# mcu.net
KiCad netlist of a schematic drawn in Altium Designer
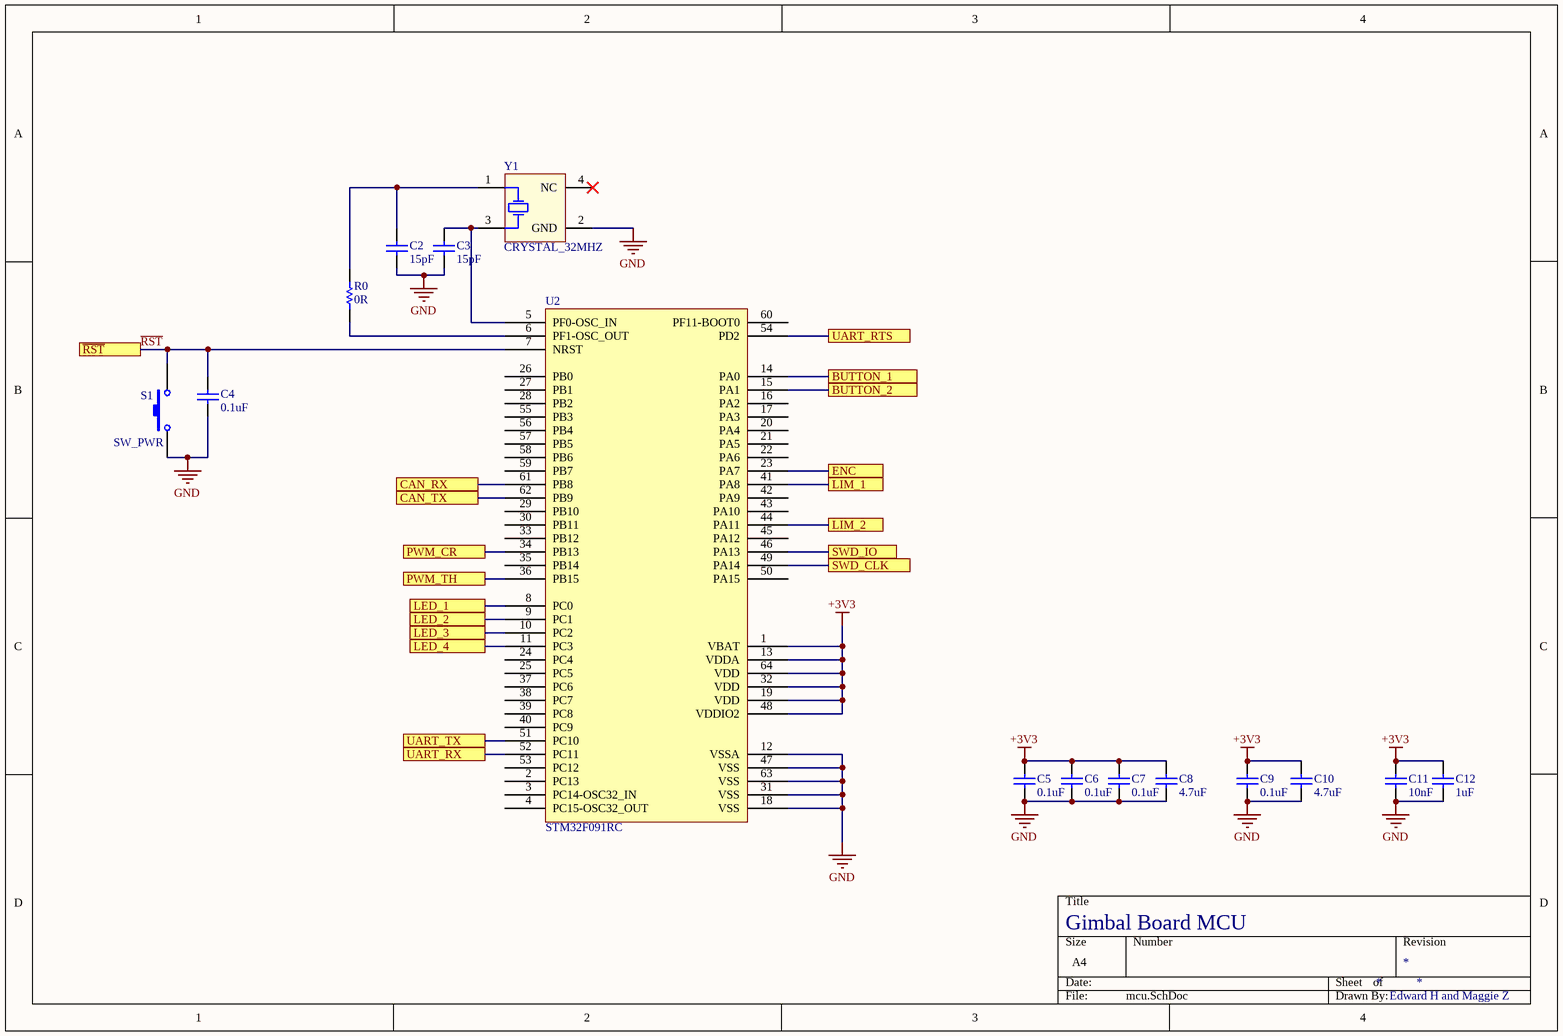
[diagram p0: mcu.SchDoc]

(export (version "E")
  (design (tool "Eeschema 10.0.6"))
  (components
    (comp (ref "C2")
      (value "15pF")
      (footprint "CAPC0603(1608)55_N")
      (description "CAP CER 15PF 250V NPO 0603")
      (fields (field (name "MANUFACTURER") "Yageo") (field (name "MPN") "AC0603JRNPOYBN150"))
      (libsource (lib "UWRT_Schematic_Library_2019") (part "CAP_15pF_0603"))
    )
    (comp (ref "C3")
      (value "15pF")
      (footprint "CAPC0603(1608)55_N")
      (description "CAP CER 15PF 250V NPO 0603")
      (fields (field (name "MANUFACTURER") "Yageo") (field (name "MPN") "AC0603JRNPOYBN150"))
      (libsource (lib "UWRT_Schematic_Library_2019") (part "CAP_15pF_0603"))
    )
    (comp (ref "C4")
      (value "0.1uF")
      (footprint "CAPC0603(1608)55_N")
      (description "CAP CER 0.1UF 16V X7R 0603")
      (fields (field (name "MANUFACTURER") "Yageo") (field (name "MPN") "CC0603KRX7R7BB104"))
      (libsource (lib "UWRT_Schematic_Library_2019") (part "CAP_0.1uF_16V_0603"))
    )
    (comp (ref "C5")
      (value "0.1uF")
      (footprint "CAPC0603(1608)55_N")
      (description "CAP CER 0.1UF 16V X7R 0603")
      (fields (field (name "MANUFACTURER") "Yageo") (field (name "MPN") "CC0603KRX7R7BB104"))
      (libsource (lib "UWRT_Schematic_Library_2019") (part "CAP_0.1uF_16V_0603"))
    )
    (comp (ref "C6")
      (value "0.1uF")
      (footprint "CAPC0603(1608)55_N")
      (description "CAP CER 0.1UF 16V X7R 0603")
      (fields (field (name "MANUFACTURER") "Yageo") (field (name "MPN") "CC0603KRX7R7BB104"))
      (libsource (lib "UWRT_Schematic_Library_2019") (part "CAP_0.1uF_16V_0603"))
    )
    (comp (ref "C7")
      (value "0.1uF")
      (footprint "CAPC0603(1608)55_N")
      (description "CAP CER 0.1UF 16V X7R 0603")
      (fields (field (name "MANUFACTURER") "Yageo") (field (name "MPN") "CC0603KRX7R7BB104"))
      (libsource (lib "UWRT_Schematic_Library_2019") (part "CAP_0.1uF_16V_0603"))
    )
    (comp (ref "C8")
      (value "4.7uF")
      (footprint "CAPC0603(1608)55_N")
      (description "CAP CER 4.7UF 6.3V X5R 0603")
      (fields (field (name "MANUFACTURER") "Yageo") (field (name "MPN") "CC0603KRX5R5BB475"))
      (libsource (lib "UWRT_Schematic_Library_2019") (part "CAP_4.7uF_0603"))
    )
    (comp (ref "C9")
      (value "0.1uF")
      (footprint "CAPC0603(1608)55_N")
      (description "CAP CER 0.1UF 16V X7R 0603")
      (fields (field (name "MANUFACTURER") "Yageo") (field (name "MPN") "CC0603KRX7R7BB104"))
      (libsource (lib "UWRT_Schematic_Library_2019") (part "CAP_0.1uF_16V_0603"))
    )
    (comp (ref "C10")
      (value "4.7uF")
      (footprint "CAPC0603(1608)55_N")
      (description "CAP CER 4.7UF 6.3V X5R 0603")
      (fields (field (name "MANUFACTURER") "Yageo") (field (name "MPN") "CC0603KRX5R5BB475"))
      (libsource (lib "UWRT_Schematic_Library_2019") (part "CAP_4.7uF_0603"))
    )
    (comp (ref "C11")
      (value "10nF")
      (footprint "CAPC0603(1608)55_N")
      (description "CAP CER 10000PF 16V X7R 0603")
      (fields (field (name "MANUFACTURER") "Yageo") (field (name "MPN") "CC0603KRX7R7BB103"))
      (libsource (lib "UWRT_Schematic_Library_2019") (part "CAP_10nF_0603"))
    )
    (comp (ref "C12")
      (value "1uF")
      (footprint "CAPC0603(1608)55_N")
      (description "CAP CER 1UF 16V Y5V 0603")
      (fields (field (name "MANUFACTURER") "Yageo") (field (name "MPN") "CC0603ZRY5V7BB105"))
      (libsource (lib "UWRT_Schematic_Library_2019") (part "CAP_1uF_16V_0603"))
    )
    (comp (ref "R0")
      (value "0R")
      (footprint "RESC0603(1608)_N")
      (description "RES SMD 0 OHM JUMPER 1/10W 0603")
      (fields (field (name "MANUFACTURER") "Yageo") (field (name "MPN") "RC0603JR-070RL"))
      (libsource (lib "UWRT_Schematic_Library_2019") (part "RES_0R_0603"))
    )
    (comp (ref "S1")
      (value "SW_PWR")
      (footprint "PTS830GM140")
      (description "Power Switch (Red)")
      (fields
        (field (name "MPN") "PTS830GM140 SMTR LFS")
        (field (name "DIGIKEY PART NUMBER") "CKN10587CT-ND")
      )
      (libsource (lib "UWRT_Schematic_Library_2019") (part "SW_PWR"))
    )
    (comp (ref "U2")
      (value "STM32F091RC")
      (footprint "UWRT_Footprint_Library_2019:STM_LQFP64_N")
      (fields
        (field (name "MANUFACTURER") "STMicroelectronics")
        (field (name "DIGIKEY PART NUMBER") "497-15167-ND")
      )
      (libsource (lib "UWRT_Schematic_Library_2019") (part "STM32F091RC"))
    )
    (comp (ref "Y1")
      (value "CRYSTAL_32MHZ")
      (footprint "AVX-CX2520DB32000D0GEJZ1-4_V")
      (description "CRYSTAL 32MHZ 8PF SMD")
      (fields
        (field (name "MANUFACTURER") "Kyocera International Inc. Electronic Components")
        (field (name "MPN") "CX2520DB32000D0GPSC1")
      )
      (libsource (lib "UWRT_Schematic_Library_2019") (part "CRYSTAL_32MHZ"))
    )
  )
  (nets
    (net (code "1") (name "+3V3") (class "Default")
      (node (ref "C10") (pin "2") (pinfunction "2_2") (pintype "passive"))
      (node (ref "C11") (pin "2") (pinfunction "2_2") (pintype "passive"))
      (node (ref "C12") (pin "2") (pinfunction "2_2") (pintype "passive"))
      (node (ref "C5") (pin "1") (pinfunction "1_1") (pintype "passive"))
      (node (ref "C6") (pin "1") (pinfunction "1_1") (pintype "passive"))
      (node (ref "C7") (pin "1") (pinfunction "1_1") (pintype "passive"))
      (node (ref "C8") (pin "2") (pinfunction "2_2") (pintype "passive"))
      (node (ref "C9") (pin "1") (pinfunction "1_1") (pintype "passive"))
      (node (ref "U2") (pin "1") (pinfunction "VBAT_1") (pintype "passive"))
      (node (ref "U2") (pin "13") (pinfunction "VDDA_13") (pintype "passive"))
      (node (ref "U2") (pin "19") (pinfunction "VDD_19") (pintype "passive"))
      (node (ref "U2") (pin "32") (pinfunction "VDD_32") (pintype "passive"))
      (node (ref "U2") (pin "48") (pinfunction "VDDIO2_48") (pintype "passive"))
      (node (ref "U2") (pin "64") (pinfunction "VDD_64") (pintype "passive"))
    )
    (net (code "2") (name "/BUTTON_1") (class "Default")
      (node (ref "U2") (pin "14") (pinfunction "PA0_14") (pintype "passive"))
    )
    (net (code "3") (name "/BUTTON_2") (class "Default")
      (node (ref "U2") (pin "15") (pinfunction "PA1_15") (pintype "passive"))
    )
    (net (code "4") (name "/CAN_RX") (class "Default")
      (node (ref "U2") (pin "61") (pinfunction "PB8_61") (pintype "passive"))
    )
    (net (code "5") (name "/CAN_TX") (class "Default")
      (node (ref "U2") (pin "62") (pinfunction "PB9_62") (pintype "passive"))
    )
    (net (code "6") (name "/ENC") (class "Default")
      (node (ref "U2") (pin "23") (pinfunction "PA7_23") (pintype "passive"))
    )
    (net (code "7") (name "/LED_1") (class "Default")
      (node (ref "U2") (pin "8") (pinfunction "PC0_8") (pintype "passive"))
    )
    (net (code "8") (name "/LED_2") (class "Default")
      (node (ref "U2") (pin "9") (pinfunction "PC1_9") (pintype "passive"))
    )
    (net (code "9") (name "/LED_3") (class "Default")
      (node (ref "U2") (pin "10") (pinfunction "PC2_10") (pintype "passive"))
    )
    (net (code "10") (name "/LED_4") (class "Default")
      (node (ref "U2") (pin "11") (pinfunction "PC3_11") (pintype "passive"))
    )
    (net (code "11") (name "/LIM_1") (class "Default")
      (node (ref "U2") (pin "41") (pinfunction "PA8_41") (pintype "passive"))
    )
    (net (code "12") (name "/LIM_2") (class "Default")
      (node (ref "U2") (pin "44") (pinfunction "PA11_44") (pintype "passive"))
    )
    (net (code "13") (name "/PWM_CR") (class "Default")
      (node (ref "U2") (pin "34") (pinfunction "PB13_34") (pintype "passive"))
    )
    (net (code "14") (name "/PWM_TH") (class "Default")
      (node (ref "U2") (pin "36") (pinfunction "PB15_36") (pintype "passive"))
    )
    (net (code "15") (name "/SWD_CLK") (class "Default")
      (node (ref "U2") (pin "49") (pinfunction "PA14_49") (pintype "passive"))
    )
    (net (code "16") (name "/SWD_IO") (class "Default")
      (node (ref "U2") (pin "46") (pinfunction "PA13_46") (pintype "passive"))
    )
    (net (code "17") (name "/UART_RTS") (class "Default")
      (node (ref "U2") (pin "54") (pinfunction "PD2_54") (pintype "passive"))
    )
    (net (code "18") (name "/UART_RX") (class "Default")
      (node (ref "U2") (pin "52") (pinfunction "PC11_52") (pintype "passive"))
    )
    (net (code "19") (name "/UART_TX") (class "Default")
      (node (ref "U2") (pin "51") (pinfunction "PC10_51") (pintype "passive"))
    )
    (net (code "20") (name "/~{RST}") (class "Default")
      (node (ref "C4") (pin "2") (pinfunction "2_2") (pintype "passive"))
      (node (ref "S1") (pin "2") (pinfunction "2_2") (pintype "passive"))
      (node (ref "U2") (pin "7") (pinfunction "NRST_7") (pintype "passive"))
    )
    (net (code "21") (name "GND") (class "Default")
      (node (ref "C10") (pin "1") (pinfunction "1_1") (pintype "passive"))
      (node (ref "C11") (pin "1") (pinfunction "1_1") (pintype "passive"))
      (node (ref "C12") (pin "1") (pinfunction "1_1") (pintype "passive"))
      (node (ref "C2") (pin "1") (pinfunction "1_1") (pintype "passive"))
      (node (ref "C3") (pin "1") (pinfunction "1_1") (pintype "passive"))
      (node (ref "C4") (pin "1") (pinfunction "1_1") (pintype "passive"))
      (node (ref "C5") (pin "2") (pinfunction "2_2") (pintype "passive"))
      (node (ref "C6") (pin "2") (pinfunction "2_2") (pintype "passive"))
      (node (ref "C7") (pin "2") (pinfunction "2_2") (pintype "passive"))
      (node (ref "C8") (pin "1") (pinfunction "1_1") (pintype "passive"))
      (node (ref "C9") (pin "2") (pinfunction "2_2") (pintype "passive"))
      (node (ref "S1") (pin "1") (pinfunction "1_1") (pintype "passive"))
      (node (ref "U2") (pin "12") (pinfunction "VSSA_12") (pintype "passive"))
      (node (ref "U2") (pin "18") (pinfunction "VSS_18") (pintype "passive"))
      (node (ref "U2") (pin "31") (pinfunction "VSS_31") (pintype "passive"))
      (node (ref "U2") (pin "47") (pinfunction "VSS_47") (pintype "passive"))
      (node (ref "U2") (pin "63") (pinfunction "VSS_63") (pintype "passive"))
      (node (ref "Y1") (pin "2") (pinfunction "GND_2") (pintype "power_in"))
    )
    (net (code "22") (name "Net-(C2-Pad2)") (class "Default")
      (node (ref "C2") (pin "2") (pinfunction "2_2") (pintype "passive"))
      (node (ref "R0") (pin "2") (pinfunction "2_2") (pintype "passive"))
      (node (ref "Y1") (pin "1") (pinfunction "HOT_1") (pintype "passive"))
    )
    (net (code "23") (name "Net-(U2-PF0-OSC_IN)") (class "Default")
      (node (ref "C3") (pin "2") (pinfunction "2_2") (pintype "passive"))
      (node (ref "U2") (pin "5") (pinfunction "PF0-OSC_IN_5") (pintype "passive"))
      (node (ref "Y1") (pin "3") (pinfunction "HOT_3") (pintype "passive"))
    )
    (net (code "24") (name "Net-(U2-PF1-OSC_OUT)") (class "Default")
      (node (ref "R0") (pin "1") (pinfunction "1_1") (pintype "passive"))
      (node (ref "U2") (pin "6") (pinfunction "PF1-OSC_OUT_6") (pintype "passive"))
    )
    (net (code "25") (name "unconnected-(U2-PA2-Pad16)") (class "Default")
      (node (ref "U2") (pin "16") (pinfunction "PA2_16") (pintype "passive"))
    )
    (net (code "26") (name "unconnected-(U2-PA3-Pad17)") (class "Default")
      (node (ref "U2") (pin "17") (pinfunction "PA3_17") (pintype "passive"))
    )
    (net (code "27") (name "unconnected-(U2-PA4-Pad20)") (class "Default")
      (node (ref "U2") (pin "20") (pinfunction "PA4_20") (pintype "passive"))
    )
    (net (code "28") (name "unconnected-(U2-PA5-Pad21)") (class "Default")
      (node (ref "U2") (pin "21") (pinfunction "PA5_21") (pintype "passive"))
    )
    (net (code "29") (name "unconnected-(U2-PA6-Pad22)") (class "Default")
      (node (ref "U2") (pin "22") (pinfunction "PA6_22") (pintype "passive"))
    )
    (net (code "30") (name "unconnected-(U2-PA9-Pad42)") (class "Default")
      (node (ref "U2") (pin "42") (pinfunction "PA9_42") (pintype "passive"))
    )
    (net (code "31") (name "unconnected-(U2-PA10-Pad43)") (class "Default")
      (node (ref "U2") (pin "43") (pinfunction "PA10_43") (pintype "passive"))
    )
    (net (code "32") (name "unconnected-(U2-PA12-Pad45)") (class "Default")
      (node (ref "U2") (pin "45") (pinfunction "PA12_45") (pintype "passive"))
    )
    (net (code "33") (name "unconnected-(U2-PA15-Pad50)") (class "Default")
      (node (ref "U2") (pin "50") (pinfunction "PA15_50") (pintype "passive"))
    )
    (net (code "34") (name "unconnected-(U2-PB0-Pad26)") (class "Default")
      (node (ref "U2") (pin "26") (pinfunction "PB0_26") (pintype "passive"))
    )
    (net (code "35") (name "unconnected-(U2-PB1-Pad27)") (class "Default")
      (node (ref "U2") (pin "27") (pinfunction "PB1_27") (pintype "passive"))
    )
    (net (code "36") (name "unconnected-(U2-PB2-Pad28)") (class "Default")
      (node (ref "U2") (pin "28") (pinfunction "PB2_28") (pintype "passive"))
    )
    (net (code "37") (name "unconnected-(U2-PB3-Pad55)") (class "Default")
      (node (ref "U2") (pin "55") (pinfunction "PB3_55") (pintype "passive"))
    )
    (net (code "38") (name "unconnected-(U2-PB4-Pad56)") (class "Default")
      (node (ref "U2") (pin "56") (pinfunction "PB4_56") (pintype "passive"))
    )
    (net (code "39") (name "unconnected-(U2-PB5-Pad57)") (class "Default")
      (node (ref "U2") (pin "57") (pinfunction "PB5_57") (pintype "passive"))
    )
    (net (code "40") (name "unconnected-(U2-PB6-Pad58)") (class "Default")
      (node (ref "U2") (pin "58") (pinfunction "PB6_58") (pintype "passive"))
    )
    (net (code "41") (name "unconnected-(U2-PB7-Pad59)") (class "Default")
      (node (ref "U2") (pin "59") (pinfunction "PB7_59") (pintype "passive"))
    )
    (net (code "42") (name "unconnected-(U2-PB10-Pad29)") (class "Default")
      (node (ref "U2") (pin "29") (pinfunction "PB10_29") (pintype "passive"))
    )
    (net (code "43") (name "unconnected-(U2-PB11-Pad30)") (class "Default")
      (node (ref "U2") (pin "30") (pinfunction "PB11_30") (pintype "passive"))
    )
    (net (code "44") (name "unconnected-(U2-PB12-Pad33)") (class "Default")
      (node (ref "U2") (pin "33") (pinfunction "PB12_33") (pintype "passive"))
    )
    (net (code "45") (name "unconnected-(U2-PB14-Pad35)") (class "Default")
      (node (ref "U2") (pin "35") (pinfunction "PB14_35") (pintype "passive"))
    )
    (net (code "46") (name "unconnected-(U2-PC4-Pad24)") (class "Default")
      (node (ref "U2") (pin "24") (pinfunction "PC4_24") (pintype "passive"))
    )
    (net (code "47") (name "unconnected-(U2-PC5-Pad25)") (class "Default")
      (node (ref "U2") (pin "25") (pinfunction "PC5_25") (pintype "passive"))
    )
    (net (code "48") (name "unconnected-(U2-PC6-Pad37)") (class "Default")
      (node (ref "U2") (pin "37") (pinfunction "PC6_37") (pintype "passive"))
    )
    (net (code "49") (name "unconnected-(U2-PC7-Pad38)") (class "Default")
      (node (ref "U2") (pin "38") (pinfunction "PC7_38") (pintype "passive"))
    )
    (net (code "50") (name "unconnected-(U2-PC8-Pad39)") (class "Default")
      (node (ref "U2") (pin "39") (pinfunction "PC8_39") (pintype "passive"))
    )
    (net (code "51") (name "unconnected-(U2-PC9-Pad40)") (class "Default")
      (node (ref "U2") (pin "40") (pinfunction "PC9_40") (pintype "passive"))
    )
    (net (code "52") (name "unconnected-(U2-PC12-Pad53)") (class "Default")
      (node (ref "U2") (pin "53") (pinfunction "PC12_53") (pintype "passive"))
    )
    (net (code "53") (name "unconnected-(U2-PC13-Pad2)") (class "Default")
      (node (ref "U2") (pin "2") (pinfunction "PC13_2") (pintype "passive"))
    )
    (net (code "54") (name "unconnected-(U2-PC14-OSC32_IN-Pad3)") (class "Default")
      (node (ref "U2") (pin "3") (pinfunction "PC14-OSC32_IN_3") (pintype "passive"))
    )
    (net (code "55") (name "unconnected-(U2-PC15-OSC32_OUT-Pad4)") (class "Default")
      (node (ref "U2") (pin "4") (pinfunction "PC15-OSC32_OUT_4") (pintype "passive"))
    )
    (net (code "56") (name "unconnected-(U2-PF11-BOOT0-Pad60)") (class "Default")
      (node (ref "U2") (pin "60") (pinfunction "PF11-BOOT0_60") (pintype "passive"))
    )
    (net (code "57") (name "unconnected-(Y1-NC-Pad4)") (class "Default")
      (node (ref "Y1") (pin "4") (pinfunction "NC_4") (pintype "passive+no_connect"))
    )
  )
)
